# MCDU.net
KiCad netlist of a schematic drawn in EAGLE
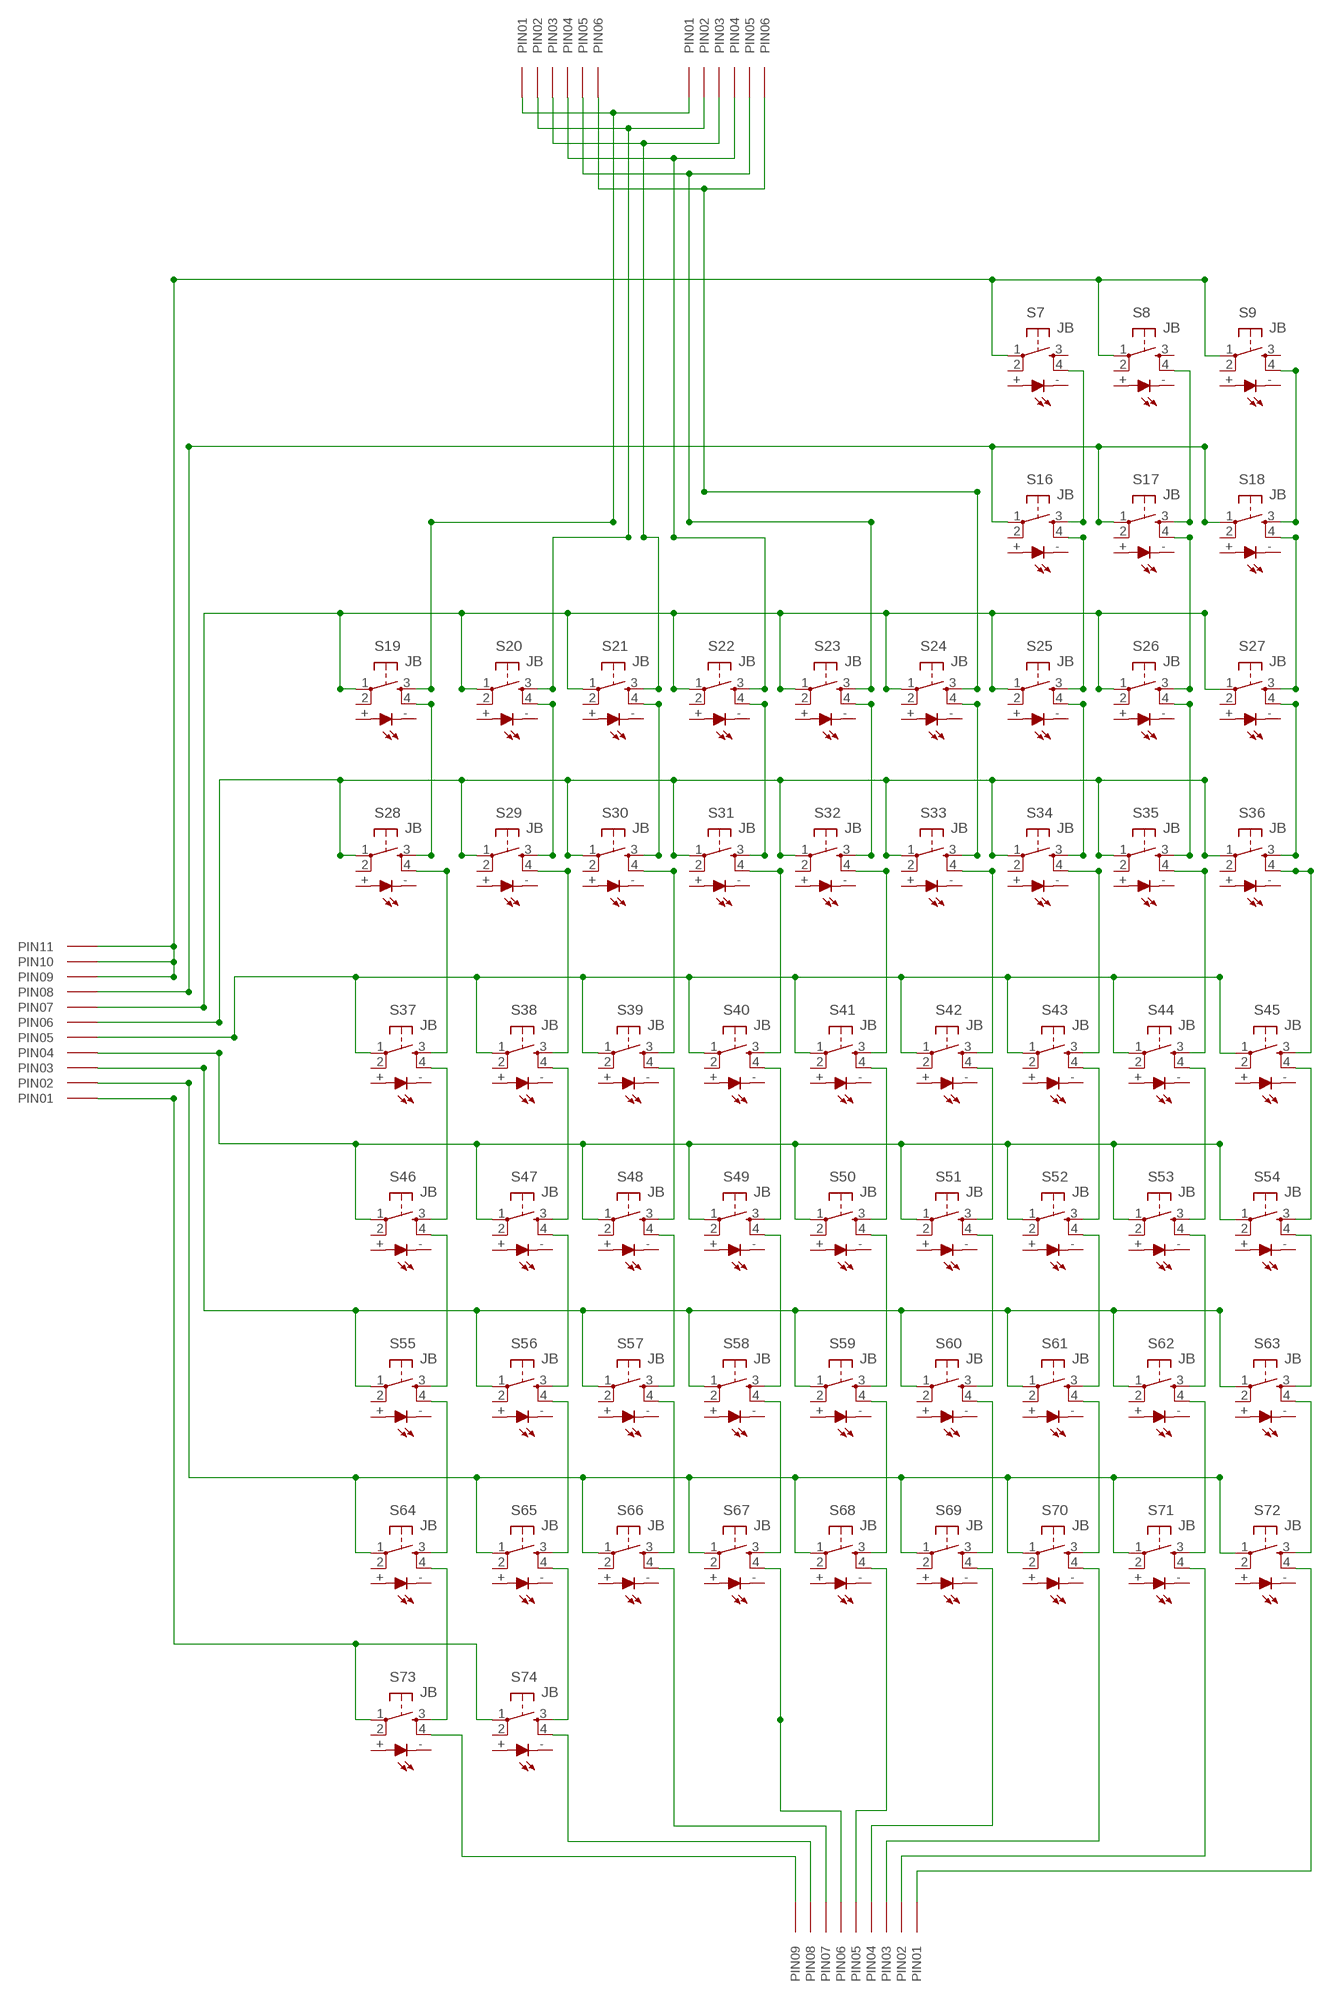
[diagram p0: schematic, sheet 1]

(export (version "E")
  (design (tool "Eeschema 10.0.6"))
  (components
    (comp (ref "S7") (value "JB") (footprint "eagle-import:JB") (libsource (lib "eagle-import") (part "JB")))
    (comp (ref "S8") (value "JB") (footprint "eagle-import:JB") (libsource (lib "eagle-import") (part "JB")))
    (comp (ref "S9") (value "JB") (footprint "eagle-import:JB") (libsource (lib "eagle-import") (part "JB")))
    (comp (ref "S16") (value "JB") (footprint "eagle-import:JB") (libsource (lib "eagle-import") (part "JB")))
    (comp (ref "S17") (value "JB") (footprint "eagle-import:JB") (libsource (lib "eagle-import") (part "JB")))
    (comp (ref "S18") (value "JB") (footprint "eagle-import:JB") (libsource (lib "eagle-import") (part "JB")))
    (comp (ref "S19") (value "JB") (footprint "eagle-import:JB") (libsource (lib "eagle-import") (part "JB")))
    (comp (ref "S20") (value "JB") (footprint "eagle-import:JB") (libsource (lib "eagle-import") (part "JB")))
    (comp (ref "S21") (value "JB") (footprint "eagle-import:JB") (libsource (lib "eagle-import") (part "JB")))
    (comp (ref "S22") (value "JB") (footprint "eagle-import:JB") (libsource (lib "eagle-import") (part "JB")))
    (comp (ref "S23") (value "JB") (footprint "eagle-import:JB") (libsource (lib "eagle-import") (part "JB")))
    (comp (ref "S24") (value "JB") (footprint "eagle-import:JB") (libsource (lib "eagle-import") (part "JB")))
    (comp (ref "S25") (value "JB") (footprint "eagle-import:JB") (libsource (lib "eagle-import") (part "JB")))
    (comp (ref "S26") (value "JB") (footprint "eagle-import:JB") (libsource (lib "eagle-import") (part "JB")))
    (comp (ref "S27") (value "JB") (footprint "eagle-import:JB") (libsource (lib "eagle-import") (part "JB")))
    (comp (ref "S28") (value "JB") (footprint "eagle-import:JB") (libsource (lib "eagle-import") (part "JB")))
    (comp (ref "S29") (value "JB") (footprint "eagle-import:JB") (libsource (lib "eagle-import") (part "JB")))
    (comp (ref "S30") (value "JB") (footprint "eagle-import:JB") (libsource (lib "eagle-import") (part "JB")))
    (comp (ref "S31") (value "JB") (footprint "eagle-import:JB") (libsource (lib "eagle-import") (part "JB")))
    (comp (ref "S32") (value "JB") (footprint "eagle-import:JB") (libsource (lib "eagle-import") (part "JB")))
    (comp (ref "S33") (value "JB") (footprint "eagle-import:JB") (libsource (lib "eagle-import") (part "JB")))
    (comp (ref "S34") (value "JB") (footprint "eagle-import:JB") (libsource (lib "eagle-import") (part "JB")))
    (comp (ref "S35") (value "JB") (footprint "eagle-import:JB") (libsource (lib "eagle-import") (part "JB")))
    (comp (ref "S36") (value "JB") (footprint "eagle-import:JB") (libsource (lib "eagle-import") (part "JB")))
    (comp (ref "S37") (value "JB") (footprint "eagle-import:JB") (libsource (lib "eagle-import") (part "JB")))
    (comp (ref "S38") (value "JB") (footprint "eagle-import:JB") (libsource (lib "eagle-import") (part "JB")))
    (comp (ref "S39") (value "JB") (footprint "eagle-import:JB") (libsource (lib "eagle-import") (part "JB")))
    (comp (ref "S40") (value "JB") (footprint "eagle-import:JB") (libsource (lib "eagle-import") (part "JB")))
    (comp (ref "S41") (value "JB") (footprint "eagle-import:JB") (libsource (lib "eagle-import") (part "JB")))
    (comp (ref "S42") (value "JB") (footprint "eagle-import:JB") (libsource (lib "eagle-import") (part "JB")))
    (comp (ref "S43") (value "JB") (footprint "eagle-import:JB") (libsource (lib "eagle-import") (part "JB")))
    (comp (ref "S44") (value "JB") (footprint "eagle-import:JB") (libsource (lib "eagle-import") (part "JB")))
    (comp (ref "S45") (value "JB") (footprint "eagle-import:JB") (libsource (lib "eagle-import") (part "JB")))
    (comp (ref "S46") (value "JB") (footprint "eagle-import:JB") (libsource (lib "eagle-import") (part "JB")))
    (comp (ref "S47") (value "JB") (footprint "eagle-import:JB") (libsource (lib "eagle-import") (part "JB")))
    (comp (ref "S48") (value "JB") (footprint "eagle-import:JB") (libsource (lib "eagle-import") (part "JB")))
    (comp (ref "S49") (value "JB") (footprint "eagle-import:JB") (libsource (lib "eagle-import") (part "JB")))
    (comp (ref "S50") (value "JB") (footprint "eagle-import:JB") (libsource (lib "eagle-import") (part "JB")))
    (comp (ref "S51") (value "JB") (footprint "eagle-import:JB") (libsource (lib "eagle-import") (part "JB")))
    (comp (ref "S52") (value "JB") (footprint "eagle-import:JB") (libsource (lib "eagle-import") (part "JB")))
    (comp (ref "S53") (value "JB") (footprint "eagle-import:JB") (libsource (lib "eagle-import") (part "JB")))
    (comp (ref "S54") (value "JB") (footprint "eagle-import:JB") (libsource (lib "eagle-import") (part "JB")))
    (comp (ref "S55") (value "JB") (footprint "eagle-import:JB") (libsource (lib "eagle-import") (part "JB")))
    (comp (ref "S56") (value "JB") (footprint "eagle-import:JB") (libsource (lib "eagle-import") (part "JB")))
    (comp (ref "S57") (value "JB") (footprint "eagle-import:JB") (libsource (lib "eagle-import") (part "JB")))
    (comp (ref "S58") (value "JB") (footprint "eagle-import:JB") (libsource (lib "eagle-import") (part "JB")))
    (comp (ref "S59") (value "JB") (footprint "eagle-import:JB") (libsource (lib "eagle-import") (part "JB")))
    (comp (ref "S60") (value "JB") (footprint "eagle-import:JB") (libsource (lib "eagle-import") (part "JB")))
    (comp (ref "S61") (value "JB") (footprint "eagle-import:JB") (libsource (lib "eagle-import") (part "JB")))
    (comp (ref "S62") (value "JB") (footprint "eagle-import:JB") (libsource (lib "eagle-import") (part "JB")))
    (comp (ref "S63") (value "JB") (footprint "eagle-import:JB") (libsource (lib "eagle-import") (part "JB")))
    (comp (ref "S64") (value "JB") (footprint "eagle-import:JB") (libsource (lib "eagle-import") (part "JB")))
    (comp (ref "S65") (value "JB") (footprint "eagle-import:JB") (libsource (lib "eagle-import") (part "JB")))
    (comp (ref "S66") (value "JB") (footprint "eagle-import:JB") (libsource (lib "eagle-import") (part "JB")))
    (comp (ref "S67") (value "JB") (footprint "eagle-import:JB") (libsource (lib "eagle-import") (part "JB")))
    (comp (ref "S68") (value "JB") (footprint "eagle-import:JB") (libsource (lib "eagle-import") (part "JB")))
    (comp (ref "S69") (value "JB") (footprint "eagle-import:JB") (libsource (lib "eagle-import") (part "JB")))
    (comp (ref "S70") (value "JB") (footprint "eagle-import:JB") (libsource (lib "eagle-import") (part "JB")))
    (comp (ref "S71") (value "JB") (footprint "eagle-import:JB") (libsource (lib "eagle-import") (part "JB")))
    (comp (ref "S72") (value "JB") (footprint "eagle-import:JB") (libsource (lib "eagle-import") (part "JB")))
    (comp (ref "S73") (value "JB") (footprint "eagle-import:JB") (libsource (lib "eagle-import") (part "JB")))
    (comp (ref "S74") (value "JB") (footprint "eagle-import:JB") (libsource (lib "eagle-import") (part "JB")))
    (comp (ref "U$2")
      (value "11PINOS")
      (footprint "eagle-import:11PINOS")
      (libsource (lib "eagle-import") (part "11PINOS"))
    )
    (comp (ref "U$3")
      (value "09PINOS")
      (footprint "eagle-import:09PINOS")
      (libsource (lib "eagle-import") (part "09PINOS"))
    )
    (comp (ref "U$5")
      (value "06PINOS")
      (footprint "eagle-import:06PINOS")
      (libsource (lib "eagle-import") (part "06PINOS"))
    )
    (comp (ref "U$6")
      (value "06PINOS")
      (footprint "eagle-import:06PINOS")
      (libsource (lib "eagle-import") (part "06PINOS"))
    )
  )
  (nets
    (net (code "1") (name "Net-(S7-P)") (class "Default")
      (node (ref "S7") (pin "1") (pinfunction "P_1") (pintype "passive"))
      (node (ref "S8") (pin "1") (pinfunction "P_1") (pintype "passive"))
      (node (ref "S9") (pin "1") (pinfunction "P_1") (pintype "passive"))
      (node (ref "U$2") (pin "PIN09") (pinfunction "PIN09_PIN09") (pintype "bidirectional"))
      (node (ref "U$2") (pin "PIN10") (pinfunction "PIN10_PIN10") (pintype "bidirectional"))
      (node (ref "U$2") (pin "PIN11") (pinfunction "PIN11_PIN11") (pintype "bidirectional"))
    )
    (net (code "2") (name "Net-(S16-P)") (class "Default")
      (node (ref "S16") (pin "1") (pinfunction "P_1") (pintype "passive"))
      (node (ref "S17") (pin "1") (pinfunction "P_1") (pintype "passive"))
      (node (ref "S18") (pin "1") (pinfunction "P_1") (pintype "passive"))
      (node (ref "U$2") (pin "PIN08") (pinfunction "PIN08_PIN08") (pintype "bidirectional"))
    )
    (net (code "3") (name "Net-(S16-S)") (class "Default")
      (node (ref "S16") (pin "3") (pinfunction "S_3") (pintype "passive"))
      (node (ref "S7") (pin "4") (pinfunction "S1_4") (pintype "passive"))
    )
    (net (code "4") (name "Net-(S16-S1)") (class "Default")
      (node (ref "S16") (pin "4") (pinfunction "S1_4") (pintype "passive"))
      (node (ref "S25") (pin "3") (pinfunction "S_3") (pintype "passive"))
    )
    (net (code "5") (name "Net-(S17-S)") (class "Default")
      (node (ref "S17") (pin "3") (pinfunction "S_3") (pintype "passive"))
      (node (ref "S8") (pin "4") (pinfunction "S1_4") (pintype "passive"))
    )
    (net (code "6") (name "Net-(S17-S1)") (class "Default")
      (node (ref "S17") (pin "4") (pinfunction "S1_4") (pintype "passive"))
      (node (ref "S26") (pin "3") (pinfunction "S_3") (pintype "passive"))
    )
    (net (code "7") (name "Net-(S18-S)") (class "Default")
      (node (ref "S18") (pin "3") (pinfunction "S_3") (pintype "passive"))
      (node (ref "S9") (pin "4") (pinfunction "S1_4") (pintype "passive"))
    )
    (net (code "8") (name "Net-(S18-S1)") (class "Default")
      (node (ref "S18") (pin "4") (pinfunction "S1_4") (pintype "passive"))
      (node (ref "S27") (pin "3") (pinfunction "S_3") (pintype "passive"))
    )
    (net (code "9") (name "Net-(S19-P)") (class "Default")
      (node (ref "S19") (pin "1") (pinfunction "P_1") (pintype "passive"))
      (node (ref "S20") (pin "1") (pinfunction "P_1") (pintype "passive"))
      (node (ref "S21") (pin "1") (pinfunction "P_1") (pintype "passive"))
      (node (ref "S22") (pin "1") (pinfunction "P_1") (pintype "passive"))
      (node (ref "S23") (pin "1") (pinfunction "P_1") (pintype "passive"))
      (node (ref "S24") (pin "1") (pinfunction "P_1") (pintype "passive"))
      (node (ref "S25") (pin "1") (pinfunction "P_1") (pintype "passive"))
      (node (ref "S26") (pin "1") (pinfunction "P_1") (pintype "passive"))
      (node (ref "S27") (pin "1") (pinfunction "P_1") (pintype "passive"))
      (node (ref "U$2") (pin "PIN07") (pinfunction "PIN07_PIN07") (pintype "bidirectional"))
    )
    (net (code "10") (name "Net-(S19-S)") (class "Default")
      (node (ref "S19") (pin "3") (pinfunction "S_3") (pintype "passive"))
      (node (ref "U$5") (pin "PIN01") (pinfunction "PIN01_PIN01") (pintype "bidirectional"))
      (node (ref "U$6") (pin "PIN01") (pinfunction "PIN01_PIN01") (pintype "bidirectional"))
    )
    (net (code "11") (name "Net-(S19-S1)") (class "Default")
      (node (ref "S19") (pin "4") (pinfunction "S1_4") (pintype "passive"))
      (node (ref "S28") (pin "3") (pinfunction "S_3") (pintype "passive"))
    )
    (net (code "12") (name "Net-(S20-S)") (class "Default")
      (node (ref "S20") (pin "3") (pinfunction "S_3") (pintype "passive"))
      (node (ref "U$5") (pin "PIN02") (pinfunction "PIN02_PIN02") (pintype "bidirectional"))
      (node (ref "U$6") (pin "PIN02") (pinfunction "PIN02_PIN02") (pintype "bidirectional"))
    )
    (net (code "13") (name "Net-(S20-S1)") (class "Default")
      (node (ref "S20") (pin "4") (pinfunction "S1_4") (pintype "passive"))
      (node (ref "S29") (pin "3") (pinfunction "S_3") (pintype "passive"))
    )
    (net (code "14") (name "Net-(S21-S)") (class "Default")
      (node (ref "S21") (pin "3") (pinfunction "S_3") (pintype "passive"))
      (node (ref "U$5") (pin "PIN03") (pinfunction "PIN03_PIN03") (pintype "bidirectional"))
      (node (ref "U$6") (pin "PIN03") (pinfunction "PIN03_PIN03") (pintype "bidirectional"))
    )
    (net (code "15") (name "Net-(S21-S1)") (class "Default")
      (node (ref "S21") (pin "4") (pinfunction "S1_4") (pintype "passive"))
      (node (ref "S30") (pin "3") (pinfunction "S_3") (pintype "passive"))
    )
    (net (code "16") (name "Net-(S22-S)") (class "Default")
      (node (ref "S22") (pin "3") (pinfunction "S_3") (pintype "passive"))
      (node (ref "U$5") (pin "PIN04") (pinfunction "PIN04_PIN04") (pintype "bidirectional"))
      (node (ref "U$6") (pin "PIN04") (pinfunction "PIN04_PIN04") (pintype "bidirectional"))
    )
    (net (code "17") (name "Net-(S22-S1)") (class "Default")
      (node (ref "S22") (pin "4") (pinfunction "S1_4") (pintype "passive"))
      (node (ref "S31") (pin "3") (pinfunction "S_3") (pintype "passive"))
    )
    (net (code "18") (name "Net-(S23-S)") (class "Default")
      (node (ref "S23") (pin "3") (pinfunction "S_3") (pintype "passive"))
      (node (ref "U$5") (pin "PIN05") (pinfunction "PIN05_PIN05") (pintype "bidirectional"))
      (node (ref "U$6") (pin "PIN05") (pinfunction "PIN05_PIN05") (pintype "bidirectional"))
    )
    (net (code "19") (name "Net-(S23-S1)") (class "Default")
      (node (ref "S23") (pin "4") (pinfunction "S1_4") (pintype "passive"))
      (node (ref "S32") (pin "3") (pinfunction "S_3") (pintype "passive"))
    )
    (net (code "20") (name "Net-(S24-S)") (class "Default")
      (node (ref "S24") (pin "3") (pinfunction "S_3") (pintype "passive"))
      (node (ref "U$5") (pin "PIN06") (pinfunction "PIN06_PIN06") (pintype "bidirectional"))
      (node (ref "U$6") (pin "PIN06") (pinfunction "PIN06_PIN06") (pintype "bidirectional"))
    )
    (net (code "21") (name "Net-(S24-S1)") (class "Default")
      (node (ref "S24") (pin "4") (pinfunction "S1_4") (pintype "passive"))
      (node (ref "S33") (pin "3") (pinfunction "S_3") (pintype "passive"))
    )
    (net (code "22") (name "Net-(S25-S1)") (class "Default")
      (node (ref "S25") (pin "4") (pinfunction "S1_4") (pintype "passive"))
      (node (ref "S34") (pin "3") (pinfunction "S_3") (pintype "passive"))
    )
    (net (code "23") (name "Net-(S26-S1)") (class "Default")
      (node (ref "S26") (pin "4") (pinfunction "S1_4") (pintype "passive"))
      (node (ref "S35") (pin "3") (pinfunction "S_3") (pintype "passive"))
    )
    (net (code "24") (name "Net-(S27-S1)") (class "Default")
      (node (ref "S27") (pin "4") (pinfunction "S1_4") (pintype "passive"))
      (node (ref "S36") (pin "3") (pinfunction "S_3") (pintype "passive"))
    )
    (net (code "25") (name "Net-(S28-P)") (class "Default")
      (node (ref "S28") (pin "1") (pinfunction "P_1") (pintype "passive"))
      (node (ref "S29") (pin "1") (pinfunction "P_1") (pintype "passive"))
      (node (ref "S30") (pin "1") (pinfunction "P_1") (pintype "passive"))
      (node (ref "S31") (pin "1") (pinfunction "P_1") (pintype "passive"))
      (node (ref "S32") (pin "1") (pinfunction "P_1") (pintype "passive"))
      (node (ref "S33") (pin "1") (pinfunction "P_1") (pintype "passive"))
      (node (ref "S34") (pin "1") (pinfunction "P_1") (pintype "passive"))
      (node (ref "S35") (pin "1") (pinfunction "P_1") (pintype "passive"))
      (node (ref "S36") (pin "1") (pinfunction "P_1") (pintype "passive"))
      (node (ref "U$2") (pin "PIN06") (pinfunction "PIN06_PIN06") (pintype "bidirectional"))
    )
    (net (code "26") (name "Net-(S28-S1)") (class "Default")
      (node (ref "S28") (pin "4") (pinfunction "S1_4") (pintype "passive"))
      (node (ref "S37") (pin "3") (pinfunction "S_3") (pintype "passive"))
    )
    (net (code "27") (name "Net-(S29-S1)") (class "Default")
      (node (ref "S29") (pin "4") (pinfunction "S1_4") (pintype "passive"))
      (node (ref "S38") (pin "3") (pinfunction "S_3") (pintype "passive"))
    )
    (net (code "28") (name "Net-(S30-S1)") (class "Default")
      (node (ref "S30") (pin "4") (pinfunction "S1_4") (pintype "passive"))
      (node (ref "S39") (pin "3") (pinfunction "S_3") (pintype "passive"))
    )
    (net (code "29") (name "Net-(S31-S1)") (class "Default")
      (node (ref "S31") (pin "4") (pinfunction "S1_4") (pintype "passive"))
      (node (ref "S40") (pin "3") (pinfunction "S_3") (pintype "passive"))
    )
    (net (code "30") (name "Net-(S32-S1)") (class "Default")
      (node (ref "S32") (pin "4") (pinfunction "S1_4") (pintype "passive"))
      (node (ref "S41") (pin "3") (pinfunction "S_3") (pintype "passive"))
    )
    (net (code "31") (name "Net-(S33-S1)") (class "Default")
      (node (ref "S33") (pin "4") (pinfunction "S1_4") (pintype "passive"))
      (node (ref "S42") (pin "3") (pinfunction "S_3") (pintype "passive"))
    )
    (net (code "32") (name "Net-(S34-S1)") (class "Default")
      (node (ref "S34") (pin "4") (pinfunction "S1_4") (pintype "passive"))
      (node (ref "S43") (pin "3") (pinfunction "S_3") (pintype "passive"))
    )
    (net (code "33") (name "Net-(S35-S1)") (class "Default")
      (node (ref "S35") (pin "4") (pinfunction "S1_4") (pintype "passive"))
      (node (ref "S44") (pin "3") (pinfunction "S_3") (pintype "passive"))
    )
    (net (code "34") (name "Net-(S36-S1)") (class "Default")
      (node (ref "S36") (pin "4") (pinfunction "S1_4") (pintype "passive"))
      (node (ref "S45") (pin "3") (pinfunction "S_3") (pintype "passive"))
    )
    (net (code "35") (name "Net-(S37-P)") (class "Default")
      (node (ref "S37") (pin "1") (pinfunction "P_1") (pintype "passive"))
      (node (ref "S38") (pin "1") (pinfunction "P_1") (pintype "passive"))
      (node (ref "S39") (pin "1") (pinfunction "P_1") (pintype "passive"))
      (node (ref "S40") (pin "1") (pinfunction "P_1") (pintype "passive"))
      (node (ref "S41") (pin "1") (pinfunction "P_1") (pintype "passive"))
      (node (ref "S42") (pin "1") (pinfunction "P_1") (pintype "passive"))
      (node (ref "S43") (pin "1") (pinfunction "P_1") (pintype "passive"))
      (node (ref "S44") (pin "1") (pinfunction "P_1") (pintype "passive"))
      (node (ref "S45") (pin "1") (pinfunction "P_1") (pintype "passive"))
      (node (ref "U$2") (pin "PIN05") (pinfunction "PIN05_PIN05") (pintype "bidirectional"))
    )
    (net (code "36") (name "Net-(S37-S1)") (class "Default")
      (node (ref "S37") (pin "4") (pinfunction "S1_4") (pintype "passive"))
      (node (ref "S46") (pin "3") (pinfunction "S_3") (pintype "passive"))
    )
    (net (code "37") (name "Net-(S38-S1)") (class "Default")
      (node (ref "S38") (pin "4") (pinfunction "S1_4") (pintype "passive"))
      (node (ref "S47") (pin "3") (pinfunction "S_3") (pintype "passive"))
    )
    (net (code "38") (name "Net-(S39-S1)") (class "Default")
      (node (ref "S39") (pin "4") (pinfunction "S1_4") (pintype "passive"))
      (node (ref "S48") (pin "3") (pinfunction "S_3") (pintype "passive"))
    )
    (net (code "39") (name "Net-(S40-S1)") (class "Default")
      (node (ref "S40") (pin "4") (pinfunction "S1_4") (pintype "passive"))
      (node (ref "S49") (pin "3") (pinfunction "S_3") (pintype "passive"))
    )
    (net (code "40") (name "Net-(S41-S1)") (class "Default")
      (node (ref "S41") (pin "4") (pinfunction "S1_4") (pintype "passive"))
      (node (ref "S50") (pin "3") (pinfunction "S_3") (pintype "passive"))
    )
    (net (code "41") (name "Net-(S42-S1)") (class "Default")
      (node (ref "S42") (pin "4") (pinfunction "S1_4") (pintype "passive"))
      (node (ref "S51") (pin "3") (pinfunction "S_3") (pintype "passive"))
    )
    (net (code "42") (name "Net-(S43-S1)") (class "Default")
      (node (ref "S43") (pin "4") (pinfunction "S1_4") (pintype "passive"))
      (node (ref "S52") (pin "3") (pinfunction "S_3") (pintype "passive"))
    )
    (net (code "43") (name "Net-(S44-S1)") (class "Default")
      (node (ref "S44") (pin "4") (pinfunction "S1_4") (pintype "passive"))
      (node (ref "S53") (pin "3") (pinfunction "S_3") (pintype "passive"))
    )
    (net (code "44") (name "Net-(S45-S1)") (class "Default")
      (node (ref "S45") (pin "4") (pinfunction "S1_4") (pintype "passive"))
      (node (ref "S54") (pin "3") (pinfunction "S_3") (pintype "passive"))
    )
    (net (code "45") (name "Net-(S46-P)") (class "Default")
      (node (ref "S46") (pin "1") (pinfunction "P_1") (pintype "passive"))
      (node (ref "S47") (pin "1") (pinfunction "P_1") (pintype "passive"))
      (node (ref "S48") (pin "1") (pinfunction "P_1") (pintype "passive"))
      (node (ref "S49") (pin "1") (pinfunction "P_1") (pintype "passive"))
      (node (ref "S50") (pin "1") (pinfunction "P_1") (pintype "passive"))
      (node (ref "S51") (pin "1") (pinfunction "P_1") (pintype "passive"))
      (node (ref "S52") (pin "1") (pinfunction "P_1") (pintype "passive"))
      (node (ref "S53") (pin "1") (pinfunction "P_1") (pintype "passive"))
      (node (ref "S54") (pin "1") (pinfunction "P_1") (pintype "passive"))
      (node (ref "U$2") (pin "PIN04") (pinfunction "PIN04_PIN04") (pintype "bidirectional"))
    )
    (net (code "46") (name "Net-(S46-S1)") (class "Default")
      (node (ref "S46") (pin "4") (pinfunction "S1_4") (pintype "passive"))
      (node (ref "S55") (pin "3") (pinfunction "S_3") (pintype "passive"))
    )
    (net (code "47") (name "Net-(S47-S1)") (class "Default")
      (node (ref "S47") (pin "4") (pinfunction "S1_4") (pintype "passive"))
      (node (ref "S56") (pin "3") (pinfunction "S_3") (pintype "passive"))
    )
    (net (code "48") (name "Net-(S48-S1)") (class "Default")
      (node (ref "S48") (pin "4") (pinfunction "S1_4") (pintype "passive"))
      (node (ref "S57") (pin "3") (pinfunction "S_3") (pintype "passive"))
    )
    (net (code "49") (name "Net-(S49-S1)") (class "Default")
      (node (ref "S49") (pin "4") (pinfunction "S1_4") (pintype "passive"))
      (node (ref "S58") (pin "3") (pinfunction "S_3") (pintype "passive"))
    )
    (net (code "50") (name "Net-(S50-S1)") (class "Default")
      (node (ref "S50") (pin "4") (pinfunction "S1_4") (pintype "passive"))
      (node (ref "S59") (pin "3") (pinfunction "S_3") (pintype "passive"))
    )
    (net (code "51") (name "Net-(S51-S1)") (class "Default")
      (node (ref "S51") (pin "4") (pinfunction "S1_4") (pintype "passive"))
      (node (ref "S60") (pin "3") (pinfunction "S_3") (pintype "passive"))
    )
    (net (code "52") (name "Net-(S52-S1)") (class "Default")
      (node (ref "S52") (pin "4") (pinfunction "S1_4") (pintype "passive"))
      (node (ref "S61") (pin "3") (pinfunction "S_3") (pintype "passive"))
    )
    (net (code "53") (name "Net-(S53-S1)") (class "Default")
      (node (ref "S53") (pin "4") (pinfunction "S1_4") (pintype "passive"))
      (node (ref "S62") (pin "3") (pinfunction "S_3") (pintype "passive"))
    )
    (net (code "54") (name "Net-(S54-S1)") (class "Default")
      (node (ref "S54") (pin "4") (pinfunction "S1_4") (pintype "passive"))
      (node (ref "S63") (pin "3") (pinfunction "S_3") (pintype "passive"))
    )
    (net (code "55") (name "Net-(S55-P)") (class "Default")
      (node (ref "S55") (pin "1") (pinfunction "P_1") (pintype "passive"))
      (node (ref "S56") (pin "1") (pinfunction "P_1") (pintype "passive"))
      (node (ref "S57") (pin "1") (pinfunction "P_1") (pintype "passive"))
      (node (ref "S58") (pin "1") (pinfunction "P_1") (pintype "passive"))
      (node (ref "S59") (pin "1") (pinfunction "P_1") (pintype "passive"))
      (node (ref "S60") (pin "1") (pinfunction "P_1") (pintype "passive"))
      (node (ref "S61") (pin "1") (pinfunction "P_1") (pintype "passive"))
      (node (ref "S62") (pin "1") (pinfunction "P_1") (pintype "passive"))
      (node (ref "S63") (pin "1") (pinfunction "P_1") (pintype "passive"))
      (node (ref "U$2") (pin "PIN03") (pinfunction "PIN03_PIN03") (pintype "bidirectional"))
    )
    (net (code "56") (name "Net-(S55-S1)") (class "Default")
      (node (ref "S55") (pin "4") (pinfunction "S1_4") (pintype "passive"))
      (node (ref "S64") (pin "3") (pinfunction "S_3") (pintype "passive"))
    )
    (net (code "57") (name "Net-(S56-S1)") (class "Default")
      (node (ref "S56") (pin "4") (pinfunction "S1_4") (pintype "passive"))
      (node (ref "S65") (pin "3") (pinfunction "S_3") (pintype "passive"))
    )
    (net (code "58") (name "Net-(S57-S1)") (class "Default")
      (node (ref "S57") (pin "4") (pinfunction "S1_4") (pintype "passive"))
      (node (ref "S66") (pin "3") (pinfunction "S_3") (pintype "passive"))
    )
    (net (code "59") (name "Net-(S58-S1)") (class "Default")
      (node (ref "S58") (pin "4") (pinfunction "S1_4") (pintype "passive"))
      (node (ref "S67") (pin "3") (pinfunction "S_3") (pintype "passive"))
    )
    (net (code "60") (name "Net-(S59-S1)") (class "Default")
      (node (ref "S59") (pin "4") (pinfunction "S1_4") (pintype "passive"))
      (node (ref "S68") (pin "3") (pinfunction "S_3") (pintype "passive"))
    )
    (net (code "61") (name "Net-(S60-S1)") (class "Default")
      (node (ref "S60") (pin "4") (pinfunction "S1_4") (pintype "passive"))
      (node (ref "S69") (pin "3") (pinfunction "S_3") (pintype "passive"))
    )
    (net (code "62") (name "Net-(S61-S1)") (class "Default")
      (node (ref "S61") (pin "4") (pinfunction "S1_4") (pintype "passive"))
      (node (ref "S70") (pin "3") (pinfunction "S_3") (pintype "passive"))
    )
    (net (code "63") (name "Net-(S62-S1)") (class "Default")
      (node (ref "S62") (pin "4") (pinfunction "S1_4") (pintype "passive"))
      (node (ref "S71") (pin "3") (pinfunction "S_3") (pintype "passive"))
    )
    (net (code "64") (name "Net-(S63-S1)") (class "Default")
      (node (ref "S63") (pin "4") (pinfunction "S1_4") (pintype "passive"))
      (node (ref "S72") (pin "3") (pinfunction "S_3") (pintype "passive"))
    )
    (net (code "65") (name "Net-(S64-P)") (class "Default")
      (node (ref "S64") (pin "1") (pinfunction "P_1") (pintype "passive"))
      (node (ref "S65") (pin "1") (pinfunction "P_1") (pintype "passive"))
      (node (ref "S66") (pin "1") (pinfunction "P_1") (pintype "passive"))
      (node (ref "S67") (pin "1") (pinfunction "P_1") (pintype "passive"))
      (node (ref "S68") (pin "1") (pinfunction "P_1") (pintype "passive"))
      (node (ref "S69") (pin "1") (pinfunction "P_1") (pintype "passive"))
      (node (ref "S70") (pin "1") (pinfunction "P_1") (pintype "passive"))
      (node (ref "S71") (pin "1") (pinfunction "P_1") (pintype "passive"))
      (node (ref "S72") (pin "1") (pinfunction "P_1") (pintype "passive"))
      (node (ref "U$2") (pin "PIN02") (pinfunction "PIN02_PIN02") (pintype "bidirectional"))
    )
    (net (code "66") (name "Net-(S64-S1)") (class "Default")
      (node (ref "S64") (pin "4") (pinfunction "S1_4") (pintype "passive"))
      (node (ref "S73") (pin "3") (pinfunction "S_3") (pintype "passive"))
    )
    (net (code "67") (name "Net-(S65-S1)") (class "Default")
      (node (ref "S65") (pin "4") (pinfunction "S1_4") (pintype "passive"))
      (node (ref "S74") (pin "3") (pinfunction "S_3") (pintype "passive"))
    )
    (net (code "68") (name "Net-(S66-S1)") (class "Default")
      (node (ref "S66") (pin "4") (pinfunction "S1_4") (pintype "passive"))
      (node (ref "U$3") (pin "PIN07") (pinfunction "PIN07_PIN07") (pintype "bidirectional"))
    )
    (net (code "69") (name "Net-(S67-S1)") (class "Default")
      (node (ref "S67") (pin "4") (pinfunction "S1_4") (pintype "passive"))
      (node (ref "U$3") (pin "PIN06") (pinfunction "PIN06_PIN06") (pintype "bidirectional"))
    )
    (net (code "70") (name "Net-(S68-S1)") (class "Default")
      (node (ref "S68") (pin "4") (pinfunction "S1_4") (pintype "passive"))
      (node (ref "U$3") (pin "PIN05") (pinfunction "PIN05_PIN05") (pintype "bidirectional"))
    )
    (net (code "71") (name "Net-(S69-S1)") (class "Default")
      (node (ref "S69") (pin "4") (pinfunction "S1_4") (pintype "passive"))
      (node (ref "U$3") (pin "PIN04") (pinfunction "PIN04_PIN04") (pintype "bidirectional"))
    )
    (net (code "72") (name "Net-(S70-S1)") (class "Default")
      (node (ref "S70") (pin "4") (pinfunction "S1_4") (pintype "passive"))
      (node (ref "U$3") (pin "PIN03") (pinfunction "PIN03_PIN03") (pintype "bidirectional"))
    )
    (net (code "73") (name "Net-(S71-S1)") (class "Default")
      (node (ref "S71") (pin "4") (pinfunction "S1_4") (pintype "passive"))
      (node (ref "U$3") (pin "PIN02") (pinfunction "PIN02_PIN02") (pintype "bidirectional"))
    )
    (net (code "74") (name "Net-(S72-S1)") (class "Default")
      (node (ref "S72") (pin "4") (pinfunction "S1_4") (pintype "passive"))
      (node (ref "U$3") (pin "PIN01") (pinfunction "PIN01_PIN01") (pintype "bidirectional"))
    )
    (net (code "75") (name "Net-(S73-P)") (class "Default")
      (node (ref "S73") (pin "1") (pinfunction "P_1") (pintype "passive"))
      (node (ref "S74") (pin "1") (pinfunction "P_1") (pintype "passive"))
      (node (ref "U$2") (pin "PIN01") (pinfunction "PIN01_PIN01") (pintype "bidirectional"))
    )
    (net (code "76") (name "Net-(S73-S1)") (class "Default")
      (node (ref "S73") (pin "4") (pinfunction "S1_4") (pintype "passive"))
      (node (ref "U$3") (pin "PIN09") (pinfunction "PIN09_PIN09") (pintype "bidirectional"))
    )
    (net (code "77") (name "Net-(S74-S1)") (class "Default")
      (node (ref "S74") (pin "4") (pinfunction "S1_4") (pintype "passive"))
      (node (ref "U$3") (pin "PIN08") (pinfunction "PIN08_PIN08") (pintype "bidirectional"))
    )
    (net (code "78") (name "unconnected-(S7-A-Pad+)") (class "Default")
      (node (ref "S7") (pin "+") (pinfunction "A_+") (pintype "passive"))
    )
    (net (code "79") (name "unconnected-(S7-C-Pad-)") (class "Default")
      (node (ref "S7") (pin "-") (pinfunction "C_-") (pintype "passive"))
    )
    (net (code "80") (name "unconnected-(S7-P1-Pad2)") (class "Default")
      (node (ref "S7") (pin "2") (pinfunction "P1_2") (pintype "passive"))
    )
    (net (code "81") (name "unconnected-(S7-S-Pad3)") (class "Default")
      (node (ref "S7") (pin "3") (pinfunction "S_3") (pintype "passive"))
    )
    (net (code "82") (name "unconnected-(S8-A-Pad+)") (class "Default")
      (node (ref "S8") (pin "+") (pinfunction "A_+") (pintype "passive"))
    )
    (net (code "83") (name "unconnected-(S8-C-Pad-)") (class "Default")
      (node (ref "S8") (pin "-") (pinfunction "C_-") (pintype "passive"))
    )
    (net (code "84") (name "unconnected-(S8-P1-Pad2)") (class "Default")
      (node (ref "S8") (pin "2") (pinfunction "P1_2") (pintype "passive"))
    )
    (net (code "85") (name "unconnected-(S8-S-Pad3)") (class "Default")
      (node (ref "S8") (pin "3") (pinfunction "S_3") (pintype "passive"))
    )
    (net (code "86") (name "unconnected-(S9-A-Pad+)") (class "Default")
      (node (ref "S9") (pin "+") (pinfunction "A_+") (pintype "passive"))
    )
    (net (code "87") (name "unconnected-(S9-C-Pad-)") (class "Default")
      (node (ref "S9") (pin "-") (pinfunction "C_-") (pintype "passive"))
    )
    (net (code "88") (name "unconnected-(S9-P1-Pad2)") (class "Default")
      (node (ref "S9") (pin "2") (pinfunction "P1_2") (pintype "passive"))
    )
    (net (code "89") (name "unconnected-(S9-S-Pad3)") (class "Default")
      (node (ref "S9") (pin "3") (pinfunction "S_3") (pintype "passive"))
    )
    (net (code "90") (name "unconnected-(S16-A-Pad+)") (class "Default")
      (node (ref "S16") (pin "+") (pinfunction "A_+") (pintype "passive"))
    )
    (net (code "91") (name "unconnected-(S16-C-Pad-)") (class "Default")
      (node (ref "S16") (pin "-") (pinfunction "C_-") (pintype "passive"))
    )
    (net (code "92") (name "unconnected-(S16-P1-Pad2)") (class "Default")
      (node (ref "S16") (pin "2") (pinfunction "P1_2") (pintype "passive"))
    )
    (net (code "93") (name "unconnected-(S17-A-Pad+)") (class "Default")
      (node (ref "S17") (pin "+") (pinfunction "A_+") (pintype "passive"))
    )
    (net (code "94") (name "unconnected-(S17-C-Pad-)") (class "Default")
      (node (ref "S17") (pin "-") (pinfunction "C_-") (pintype "passive"))
    )
    (net (code "95") (name "unconnected-(S17-P1-Pad2)") (class "Default")
      (node (ref "S17") (pin "2") (pinfunction "P1_2") (pintype "passive"))
    )
    (net (code "96") (name "unconnected-(S18-A-Pad+)") (class "Default")
      (node (ref "S18") (pin "+") (pinfunction "A_+") (pintype "passive"))
    )
    (net (code "97") (name "unconnected-(S18-C-Pad-)") (class "Default")
      (node (ref "S18") (pin "-") (pinfunction "C_-") (pintype "passive"))
    )
    (net (code "98") (name "unconnected-(S18-P1-Pad2)") (class "Default")
      (node (ref "S18") (pin "2") (pinfunction "P1_2") (pintype "passive"))
    )
    (net (code "99") (name "unconnected-(S19-A-Pad+)") (class "Default")
      (node (ref "S19") (pin "+") (pinfunction "A_+") (pintype "passive"))
    )
    (net (code "100") (name "unconnected-(S19-C-Pad-)") (class "Default")
      (node (ref "S19") (pin "-") (pinfunction "C_-") (pintype "passive"))
    )
    (net (code "101") (name "unconnected-(S19-P1-Pad2)") (class "Default")
      (node (ref "S19") (pin "2") (pinfunction "P1_2") (pintype "passive"))
    )
    (net (code "102") (name "unconnected-(S20-A-Pad+)") (class "Default")
      (node (ref "S20") (pin "+") (pinfunction "A_+") (pintype "passive"))
    )
    (net (code "103") (name "unconnected-(S20-C-Pad-)") (class "Default")
      (node (ref "S20") (pin "-") (pinfunction "C_-") (pintype "passive"))
    )
    (net (code "104") (name "unconnected-(S20-P1-Pad2)") (class "Default")
      (node (ref "S20") (pin "2") (pinfunction "P1_2") (pintype "passive"))
    )
    (net (code "105") (name "unconnected-(S21-A-Pad+)") (class "Default")
      (node (ref "S21") (pin "+") (pinfunction "A_+") (pintype "passive"))
    )
    (net (code "106") (name "unconnected-(S21-C-Pad-)") (class "Default")
      (node (ref "S21") (pin "-") (pinfunction "C_-") (pintype "passive"))
    )
    (net (code "107") (name "unconnected-(S21-P1-Pad2)") (class "Default")
      (node (ref "S21") (pin "2") (pinfunction "P1_2") (pintype "passive"))
    )
    (net (code "108") (name "unconnected-(S22-A-Pad+)") (class "Default")
      (node (ref "S22") (pin "+") (pinfunction "A_+") (pintype "passive"))
    )
    (net (code "109") (name "unconnected-(S22-C-Pad-)") (class "Default")
      (node (ref "S22") (pin "-") (pinfunction "C_-") (pintype "passive"))
    )
    (net (code "110") (name "unconnected-(S22-P1-Pad2)") (class "Default")
      (node (ref "S22") (pin "2") (pinfunction "P1_2") (pintype "passive"))
    )
    (net (code "111") (name "unconnected-(S23-A-Pad+)") (class "Default")
      (node (ref "S23") (pin "+") (pinfunction "A_+") (pintype "passive"))
    )
    (net (code "112") (name "unconnected-(S23-C-Pad-)") (class "Default")
      (node (ref "S23") (pin "-") (pinfunction "C_-") (pintype "passive"))
    )
    (net (code "113") (name "unconnected-(S23-P1-Pad2)") (class "Default")
      (node (ref "S23") (pin "2") (pinfunction "P1_2") (pintype "passive"))
    )
    (net (code "114") (name "unconnected-(S24-A-Pad+)") (class "Default")
      (node (ref "S24") (pin "+") (pinfunction "A_+") (pintype "passive"))
    )
    (net (code "115") (name "unconnected-(S24-C-Pad-)") (class "Default")
      (node (ref "S24") (pin "-") (pinfunction "C_-") (pintype "passive"))
    )
    (net (code "116") (name "unconnected-(S24-P1-Pad2)") (class "Default")
      (node (ref "S24") (pin "2") (pinfunction "P1_2") (pintype "passive"))
    )
    (net (code "117") (name "unconnected-(S25-A-Pad+)") (class "Default")
      (node (ref "S25") (pin "+") (pinfunction "A_+") (pintype "passive"))
    )
    (net (code "118") (name "unconnected-(S25-C-Pad-)") (class "Default")
      (node (ref "S25") (pin "-") (pinfunction "C_-") (pintype "passive"))
    )
    (net (code "119") (name "unconnected-(S25-P1-Pad2)") (class "Default")
      (node (ref "S25") (pin "2") (pinfunction "P1_2") (pintype "passive"))
    )
    (net (code "120") (name "unconnected-(S26-A-Pad+)") (class "Default")
      (node (ref "S26") (pin "+") (pinfunction "A_+") (pintype "passive"))
    )
    (net (code "121") (name "unconnected-(S26-C-Pad-)") (class "Default")
      (node (ref "S26") (pin "-") (pinfunction "C_-") (pintype "passive"))
    )
    (net (code "122") (name "unconnected-(S26-P1-Pad2)") (class "Default")
      (node (ref "S26") (pin "2") (pinfunction "P1_2") (pintype "passive"))
    )
    (net (code "123") (name "unconnected-(S27-A-Pad+)") (class "Default")
      (node (ref "S27") (pin "+") (pinfunction "A_+") (pintype "passive"))
    )
    (net (code "124") (name "unconnected-(S27-C-Pad-)") (class "Default")
      (node (ref "S27") (pin "-") (pinfunction "C_-") (pintype "passive"))
    )
    (net (code "125") (name "unconnected-(S27-P1-Pad2)") (class "Default")
      (node (ref "S27") (pin "2") (pinfunction "P1_2") (pintype "passive"))
    )
    (net (code "126") (name "unconnected-(S28-A-Pad+)") (class "Default")
      (node (ref "S28") (pin "+") (pinfunction "A_+") (pintype "passive"))
    )
    (net (code "127") (name "unconnected-(S28-C-Pad-)") (class "Default")
      (node (ref "S28") (pin "-") (pinfunction "C_-") (pintype "passive"))
    )
    (net (code "128") (name "unconnected-(S28-P1-Pad2)") (class "Default")
      (node (ref "S28") (pin "2") (pinfunction "P1_2") (pintype "passive"))
    )
    (net (code "129") (name "unconnected-(S29-A-Pad+)") (class "Default")
      (node (ref "S29") (pin "+") (pinfunction "A_+") (pintype "passive"))
    )
    (net (code "130") (name "unconnected-(S29-C-Pad-)") (class "Default")
      (node (ref "S29") (pin "-") (pinfunction "C_-") (pintype "passive"))
    )
    (net (code "131") (name "unconnected-(S29-P1-Pad2)") (class "Default")
      (node (ref "S29") (pin "2") (pinfunction "P1_2") (pintype "passive"))
    )
    (net (code "132") (name "unconnected-(S30-A-Pad+)") (class "Default")
      (node (ref "S30") (pin "+") (pinfunction "A_+") (pintype "passive"))
    )
    (net (code "133") (name "unconnected-(S30-C-Pad-)") (class "Default")
      (node (ref "S30") (pin "-") (pinfunction "C_-") (pintype "passive"))
    )
    (net (code "134") (name "unconnected-(S30-P1-Pad2)") (class "Default")
      (node (ref "S30") (pin "2") (pinfunction "P1_2") (pintype "passive"))
    )
    (net (code "135") (name "unconnected-(S31-A-Pad+)") (class "Default")
      (node (ref "S31") (pin "+") (pinfunction "A_+") (pintype "passive"))
    )
    (net (code "136") (name "unconnected-(S31-C-Pad-)") (class "Default")
      (node (ref "S31") (pin "-") (pinfunction "C_-") (pintype "passive"))
    )
    (net (code "137") (name "unconnected-(S31-P1-Pad2)") (class "Default")
      (node (ref "S31") (pin "2") (pinfunction "P1_2") (pintype "passive"))
    )
    (net (code "138") (name "unconnected-(S32-A-Pad+)") (class "Default")
      (node (ref "S32") (pin "+") (pinfunction "A_+") (pintype "passive"))
    )
    (net (code "139") (name "unconnected-(S32-C-Pad-)") (class "Default")
      (node (ref "S32") (pin "-") (pinfunction "C_-") (pintype "passive"))
    )
    (net (code "140") (name "unconnected-(S32-P1-Pad2)") (class "Default")
      (node (ref "S32") (pin "2") (pinfunction "P1_2") (pintype "passive"))
    )
    (net (code "141") (name "unconnected-(S33-A-Pad+)") (class "Default")
      (node (ref "S33") (pin "+") (pinfunction "A_+") (pintype "passive"))
    )
    (net (code "142") (name "unconnected-(S33-C-Pad-)") (class "Default")
      (node (ref "S33") (pin "-") (pinfunction "C_-") (pintype "passive"))
    )
    (net (code "143") (name "unconnected-(S33-P1-Pad2)") (class "Default")
      (node (ref "S33") (pin "2") (pinfunction "P1_2") (pintype "passive"))
    )
    (net (code "144") (name "unconnected-(S34-A-Pad+)") (class "Default")
      (node (ref "S34") (pin "+") (pinfunction "A_+") (pintype "passive"))
    )
    (net (code "145") (name "unconnected-(S34-C-Pad-)") (class "Default")
      (node (ref "S34") (pin "-") (pinfunction "C_-") (pintype "passive"))
    )
    (net (code "146") (name "unconnected-(S34-P1-Pad2)") (class "Default")
      (node (ref "S34") (pin "2") (pinfunction "P1_2") (pintype "passive"))
    )
    (net (code "147") (name "unconnected-(S35-A-Pad+)") (class "Default")
      (node (ref "S35") (pin "+") (pinfunction "A_+") (pintype "passive"))
    )
    (net (code "148") (name "unconnected-(S35-C-Pad-)") (class "Default")
      (node (ref "S35") (pin "-") (pinfunction "C_-") (pintype "passive"))
    )
    (net (code "149") (name "unconnected-(S35-P1-Pad2)") (class "Default")
      (node (ref "S35") (pin "2") (pinfunction "P1_2") (pintype "passive"))
    )
    (net (code "150") (name "unconnected-(S36-A-Pad+)") (class "Default")
      (node (ref "S36") (pin "+") (pinfunction "A_+") (pintype "passive"))
    )
    (net (code "151") (name "unconnected-(S36-C-Pad-)") (class "Default")
      (node (ref "S36") (pin "-") (pinfunction "C_-") (pintype "passive"))
    )
    (net (code "152") (name "unconnected-(S36-P1-Pad2)") (class "Default")
      (node (ref "S36") (pin "2") (pinfunction "P1_2") (pintype "passive"))
    )
    (net (code "153") (name "unconnected-(S37-A-Pad+)") (class "Default")
      (node (ref "S37") (pin "+") (pinfunction "A_+") (pintype "passive"))
    )
    (net (code "154") (name "unconnected-(S37-C-Pad-)") (class "Default")
      (node (ref "S37") (pin "-") (pinfunction "C_-") (pintype "passive"))
    )
    (net (code "155") (name "unconnected-(S37-P1-Pad2)") (class "Default")
      (node (ref "S37") (pin "2") (pinfunction "P1_2") (pintype "passive"))
    )
    (net (code "156") (name "unconnected-(S38-A-Pad+)") (class "Default")
      (node (ref "S38") (pin "+") (pinfunction "A_+") (pintype "passive"))
    )
    (net (code "157") (name "unconnected-(S38-C-Pad-)") (class "Default")
      (node (ref "S38") (pin "-") (pinfunction "C_-") (pintype "passive"))
    )
    (net (code "158") (name "unconnected-(S38-P1-Pad2)") (class "Default")
      (node (ref "S38") (pin "2") (pinfunction "P1_2") (pintype "passive"))
    )
    (net (code "159") (name "unconnected-(S39-A-Pad+)") (class "Default")
      (node (ref "S39") (pin "+") (pinfunction "A_+") (pintype "passive"))
    )
    (net (code "160") (name "unconnected-(S39-C-Pad-)") (class "Default")
      (node (ref "S39") (pin "-") (pinfunction "C_-") (pintype "passive"))
    )
    (net (code "161") (name "unconnected-(S39-P1-Pad2)") (class "Default")
      (node (ref "S39") (pin "2") (pinfunction "P1_2") (pintype "passive"))
    )
    (net (code "162") (name "unconnected-(S40-A-Pad+)") (class "Default")
      (node (ref "S40") (pin "+") (pinfunction "A_+") (pintype "passive"))
    )
    (net (code "163") (name "unconnected-(S40-C-Pad-)") (class "Default")
      (node (ref "S40") (pin "-") (pinfunction "C_-") (pintype "passive"))
    )
    (net (code "164") (name "unconnected-(S40-P1-Pad2)") (class "Default")
      (node (ref "S40") (pin "2") (pinfunction "P1_2") (pintype "passive"))
    )
    (net (code "165") (name "unconnected-(S41-A-Pad+)") (class "Default")
      (node (ref "S41") (pin "+") (pinfunction "A_+") (pintype "passive"))
    )
    (net (code "166") (name "unconnected-(S41-C-Pad-)") (class "Default")
      (node (ref "S41") (pin "-") (pinfunction "C_-") (pintype "passive"))
    )
    (net (code "167") (name "unconnected-(S41-P1-Pad2)") (class "Default")
      (node (ref "S41") (pin "2") (pinfunction "P1_2") (pintype "passive"))
    )
    (net (code "168") (name "unconnected-(S42-A-Pad+)") (class "Default")
      (node (ref "S42") (pin "+") (pinfunction "A_+") (pintype "passive"))
    )
    (net (code "169") (name "unconnected-(S42-C-Pad-)") (class "Default")
      (node (ref "S42") (pin "-") (pinfunction "C_-") (pintype "passive"))
    )
    (net (code "170") (name "unconnected-(S42-P1-Pad2)") (class "Default")
      (node (ref "S42") (pin "2") (pinfunction "P1_2") (pintype "passive"))
    )
    (net (code "171") (name "unconnected-(S43-A-Pad+)") (class "Default")
      (node (ref "S43") (pin "+") (pinfunction "A_+") (pintype "passive"))
    )
    (net (code "172") (name "unconnected-(S43-C-Pad-)") (class "Default")
      (node (ref "S43") (pin "-") (pinfunction "C_-") (pintype "passive"))
    )
    (net (code "173") (name "unconnected-(S43-P1-Pad2)") (class "Default")
      (node (ref "S43") (pin "2") (pinfunction "P1_2") (pintype "passive"))
    )
    (net (code "174") (name "unconnected-(S44-A-Pad+)") (class "Default")
      (node (ref "S44") (pin "+") (pinfunction "A_+") (pintype "passive"))
    )
    (net (code "175") (name "unconnected-(S44-C-Pad-)") (class "Default")
      (node (ref "S44") (pin "-") (pinfunction "C_-") (pintype "passive"))
    )
    (net (code "176") (name "unconnected-(S44-P1-Pad2)") (class "Default")
      (node (ref "S44") (pin "2") (pinfunction "P1_2") (pintype "passive"))
    )
    (net (code "177") (name "unconnected-(S45-A-Pad+)") (class "Default")
      (node (ref "S45") (pin "+") (pinfunction "A_+") (pintype "passive"))
    )
    (net (code "178") (name "unconnected-(S45-C-Pad-)") (class "Default")
      (node (ref "S45") (pin "-") (pinfunction "C_-") (pintype "passive"))
    )
    (net (code "179") (name "unconnected-(S45-P1-Pad2)") (class "Default")
      (node (ref "S45") (pin "2") (pinfunction "P1_2") (pintype "passive"))
    )
    (net (code "180") (name "unconnected-(S46-A-Pad+)") (class "Default")
      (node (ref "S46") (pin "+") (pinfunction "A_+") (pintype "passive"))
    )
    (net (code "181") (name "unconnected-(S46-C-Pad-)") (class "Default")
      (node (ref "S46") (pin "-") (pinfunction "C_-") (pintype "passive"))
    )
    (net (code "182") (name "unconnected-(S46-P1-Pad2)") (class "Default")
      (node (ref "S46") (pin "2") (pinfunction "P1_2") (pintype "passive"))
    )
    (net (code "183") (name "unconnected-(S47-A-Pad+)") (class "Default")
      (node (ref "S47") (pin "+") (pinfunction "A_+") (pintype "passive"))
    )
    (net (code "184") (name "unconnected-(S47-C-Pad-)") (class "Default")
      (node (ref "S47") (pin "-") (pinfunction "C_-") (pintype "passive"))
    )
    (net (code "185") (name "unconnected-(S47-P1-Pad2)") (class "Default")
      (node (ref "S47") (pin "2") (pinfunction "P1_2") (pintype "passive"))
    )
    (net (code "186") (name "unconnected-(S48-A-Pad+)") (class "Default")
      (node (ref "S48") (pin "+") (pinfunction "A_+") (pintype "passive"))
    )
    (net (code "187") (name "unconnected-(S48-C-Pad-)") (class "Default")
      (node (ref "S48") (pin "-") (pinfunction "C_-") (pintype "passive"))
    )
    (net (code "188") (name "unconnected-(S48-P1-Pad2)") (class "Default")
      (node (ref "S48") (pin "2") (pinfunction "P1_2") (pintype "passive"))
    )
    (net (code "189") (name "unconnected-(S49-A-Pad+)") (class "Default")
      (node (ref "S49") (pin "+") (pinfunction "A_+") (pintype "passive"))
    )
    (net (code "190") (name "unconnected-(S49-C-Pad-)") (class "Default")
      (node (ref "S49") (pin "-") (pinfunction "C_-") (pintype "passive"))
    )
    (net (code "191") (name "unconnected-(S49-P1-Pad2)") (class "Default")
      (node (ref "S49") (pin "2") (pinfunction "P1_2") (pintype "passive"))
    )
    (net (code "192") (name "unconnected-(S50-A-Pad+)") (class "Default")
      (node (ref "S50") (pin "+") (pinfunction "A_+") (pintype "passive"))
    )
    (net (code "193") (name "unconnected-(S50-C-Pad-)") (class "Default")
      (node (ref "S50") (pin "-") (pinfunction "C_-") (pintype "passive"))
    )
    (net (code "194") (name "unconnected-(S50-P1-Pad2)") (class "Default")
      (node (ref "S50") (pin "2") (pinfunction "P1_2") (pintype "passive"))
    )
    (net (code "195") (name "unconnected-(S51-A-Pad+)") (class "Default")
      (node (ref "S51") (pin "+") (pinfunction "A_+") (pintype "passive"))
    )
    (net (code "196") (name "unconnected-(S51-C-Pad-)") (class "Default")
      (node (ref "S51") (pin "-") (pinfunction "C_-") (pintype "passive"))
    )
    (net (code "197") (name "unconnected-(S51-P1-Pad2)") (class "Default")
      (node (ref "S51") (pin "2") (pinfunction "P1_2") (pintype "passive"))
    )
    (net (code "198") (name "unconnected-(S52-A-Pad+)") (class "Default")
      (node (ref "S52") (pin "+") (pinfunction "A_+") (pintype "passive"))
    )
    (net (code "199") (name "unconnected-(S52-C-Pad-)") (class "Default")
      (node (ref "S52") (pin "-") (pinfunction "C_-") (pintype "passive"))
    )
    (net (code "200") (name "unconnected-(S52-P1-Pad2)") (class "Default")
      (node (ref "S52") (pin "2") (pinfunction "P1_2") (pintype "passive"))
    )
    (net (code "201") (name "unconnected-(S53-A-Pad+)") (class "Default")
      (node (ref "S53") (pin "+") (pinfunction "A_+") (pintype "passive"))
    )
    (net (code "202") (name "unconnected-(S53-C-Pad-)") (class "Default")
      (node (ref "S53") (pin "-") (pinfunction "C_-") (pintype "passive"))
    )
    (net (code "203") (name "unconnected-(S53-P1-Pad2)") (class "Default")
      (node (ref "S53") (pin "2") (pinfunction "P1_2") (pintype "passive"))
    )
    (net (code "204") (name "unconnected-(S54-A-Pad+)") (class "Default")
      (node (ref "S54") (pin "+") (pinfunction "A_+") (pintype "passive"))
    )
    (net (code "205") (name "unconnected-(S54-C-Pad-)") (class "Default")
      (node (ref "S54") (pin "-") (pinfunction "C_-") (pintype "passive"))
    )
    (net (code "206") (name "unconnected-(S54-P1-Pad2)") (class "Default")
      (node (ref "S54") (pin "2") (pinfunction "P1_2") (pintype "passive"))
    )
    (net (code "207") (name "unconnected-(S55-A-Pad+)") (class "Default")
      (node (ref "S55") (pin "+") (pinfunction "A_+") (pintype "passive"))
    )
    (net (code "208") (name "unconnected-(S55-C-Pad-)") (class "Default")
      (node (ref "S55") (pin "-") (pinfunction "C_-") (pintype "passive"))
    )
    (net (code "209") (name "unconnected-(S55-P1-Pad2)") (class "Default")
      (node (ref "S55") (pin "2") (pinfunction "P1_2") (pintype "passive"))
    )
    (net (code "210") (name "unconnected-(S56-A-Pad+)") (class "Default")
      (node (ref "S56") (pin "+") (pinfunction "A_+") (pintype "passive"))
    )
    (net (code "211") (name "unconnected-(S56-C-Pad-)") (class "Default")
      (node (ref "S56") (pin "-") (pinfunction "C_-") (pintype "passive"))
    )
    (net (code "212") (name "unconnected-(S56-P1-Pad2)") (class "Default")
      (node (ref "S56") (pin "2") (pinfunction "P1_2") (pintype "passive"))
    )
    (net (code "213") (name "unconnected-(S57-A-Pad+)") (class "Default")
      (node (ref "S57") (pin "+") (pinfunction "A_+") (pintype "passive"))
    )
    (net (code "214") (name "unconnected-(S57-C-Pad-)") (class "Default")
      (node (ref "S57") (pin "-") (pinfunction "C_-") (pintype "passive"))
    )
    (net (code "215") (name "unconnected-(S57-P1-Pad2)") (class "Default")
      (node (ref "S57") (pin "2") (pinfunction "P1_2") (pintype "passive"))
    )
    (net (code "216") (name "unconnected-(S58-A-Pad+)") (class "Default")
      (node (ref "S58") (pin "+") (pinfunction "A_+") (pintype "passive"))
    )
    (net (code "217") (name "unconnected-(S58-C-Pad-)") (class "Default")
      (node (ref "S58") (pin "-") (pinfunction "C_-") (pintype "passive"))
    )
    (net (code "218") (name "unconnected-(S58-P1-Pad2)") (class "Default")
      (node (ref "S58") (pin "2") (pinfunction "P1_2") (pintype "passive"))
    )
    (net (code "219") (name "unconnected-(S59-A-Pad+)") (class "Default")
      (node (ref "S59") (pin "+") (pinfunction "A_+") (pintype "passive"))
    )
    (net (code "220") (name "unconnected-(S59-C-Pad-)") (class "Default")
      (node (ref "S59") (pin "-") (pinfunction "C_-") (pintype "passive"))
    )
    (net (code "221") (name "unconnected-(S59-P1-Pad2)") (class "Default")
      (node (ref "S59") (pin "2") (pinfunction "P1_2") (pintype "passive"))
    )
    (net (code "222") (name "unconnected-(S60-A-Pad+)") (class "Default")
      (node (ref "S60") (pin "+") (pinfunction "A_+") (pintype "passive"))
    )
    (net (code "223") (name "unconnected-(S60-C-Pad-)") (class "Default")
      (node (ref "S60") (pin "-") (pinfunction "C_-") (pintype "passive"))
    )
    (net (code "224") (name "unconnected-(S60-P1-Pad2)") (class "Default")
      (node (ref "S60") (pin "2") (pinfunction "P1_2") (pintype "passive"))
    )
    (net (code "225") (name "unconnected-(S61-A-Pad+)") (class "Default")
      (node (ref "S61") (pin "+") (pinfunction "A_+") (pintype "passive"))
    )
    (net (code "226") (name "unconnected-(S61-C-Pad-)") (class "Default")
      (node (ref "S61") (pin "-") (pinfunction "C_-") (pintype "passive"))
    )
    (net (code "227") (name "unconnected-(S61-P1-Pad2)") (class "Default")
      (node (ref "S61") (pin "2") (pinfunction "P1_2") (pintype "passive"))
    )
    (net (code "228") (name "unconnected-(S62-A-Pad+)") (class "Default")
      (node (ref "S62") (pin "+") (pinfunction "A_+") (pintype "passive"))
    )
    (net (code "229") (name "unconnected-(S62-C-Pad-)") (class "Default")
      (node (ref "S62") (pin "-") (pinfunction "C_-") (pintype "passive"))
    )
    (net (code "230") (name "unconnected-(S62-P1-Pad2)") (class "Default")
      (node (ref "S62") (pin "2") (pinfunction "P1_2") (pintype "passive"))
    )
    (net (code "231") (name "unconnected-(S63-A-Pad+)") (class "Default")
      (node (ref "S63") (pin "+") (pinfunction "A_+") (pintype "passive"))
    )
    (net (code "232") (name "unconnected-(S63-C-Pad-)") (class "Default")
      (node (ref "S63") (pin "-") (pinfunction "C_-") (pintype "passive"))
    )
    (net (code "233") (name "unconnected-(S63-P1-Pad2)") (class "Default")
      (node (ref "S63") (pin "2") (pinfunction "P1_2") (pintype "passive"))
    )
    (net (code "234") (name "unconnected-(S64-A-Pad+)") (class "Default")
      (node (ref "S64") (pin "+") (pinfunction "A_+") (pintype "passive"))
    )
    (net (code "235") (name "unconnected-(S64-C-Pad-)") (class "Default")
      (node (ref "S64") (pin "-") (pinfunction "C_-") (pintype "passive"))
    )
    (net (code "236") (name "unconnected-(S64-P1-Pad2)") (class "Default")
      (node (ref "S64") (pin "2") (pinfunction "P1_2") (pintype "passive"))
    )
    (net (code "237") (name "unconnected-(S65-A-Pad+)") (class "Default")
      (node (ref "S65") (pin "+") (pinfunction "A_+") (pintype "passive"))
    )
    (net (code "238") (name "unconnected-(S65-C-Pad-)") (class "Default")
      (node (ref "S65") (pin "-") (pinfunction "C_-") (pintype "passive"))
    )
    (net (code "239") (name "unconnected-(S65-P1-Pad2)") (class "Default")
      (node (ref "S65") (pin "2") (pinfunction "P1_2") (pintype "passive"))
    )
    (net (code "240") (name "unconnected-(S66-A-Pad+)") (class "Default")
      (node (ref "S66") (pin "+") (pinfunction "A_+") (pintype "passive"))
    )
    (net (code "241") (name "unconnected-(S66-C-Pad-)") (class "Default")
      (node (ref "S66") (pin "-") (pinfunction "C_-") (pintype "passive"))
    )
    (net (code "242") (name "unconnected-(S66-P1-Pad2)") (class "Default")
      (node (ref "S66") (pin "2") (pinfunction "P1_2") (pintype "passive"))
    )
    (net (code "243") (name "unconnected-(S67-A-Pad+)") (class "Default")
      (node (ref "S67") (pin "+") (pinfunction "A_+") (pintype "passive"))
    )
    (net (code "244") (name "unconnected-(S67-C-Pad-)") (class "Default")
      (node (ref "S67") (pin "-") (pinfunction "C_-") (pintype "passive"))
    )
    (net (code "245") (name "unconnected-(S67-P1-Pad2)") (class "Default")
      (node (ref "S67") (pin "2") (pinfunction "P1_2") (pintype "passive"))
    )
    (net (code "246") (name "unconnected-(S68-A-Pad+)") (class "Default")
      (node (ref "S68") (pin "+") (pinfunction "A_+") (pintype "passive"))
    )
    (net (code "247") (name "unconnected-(S68-C-Pad-)") (class "Default")
      (node (ref "S68") (pin "-") (pinfunction "C_-") (pintype "passive"))
    )
    (net (code "248") (name "unconnected-(S68-P1-Pad2)") (class "Default")
      (node (ref "S68") (pin "2") (pinfunction "P1_2") (pintype "passive"))
    )
    (net (code "249") (name "unconnected-(S69-A-Pad+)") (class "Default")
      (node (ref "S69") (pin "+") (pinfunction "A_+") (pintype "passive"))
    )
    (net (code "250") (name "unconnected-(S69-C-Pad-)") (class "Default")
      (node (ref "S69") (pin "-") (pinfunction "C_-") (pintype "passive"))
    )
    (net (code "251") (name "unconnected-(S69-P1-Pad2)") (class "Default")
      (node (ref "S69") (pin "2") (pinfunction "P1_2") (pintype "passive"))
    )
    (net (code "252") (name "unconnected-(S70-A-Pad+)") (class "Default")
      (node (ref "S70") (pin "+") (pinfunction "A_+") (pintype "passive"))
    )
    (net (code "253") (name "unconnected-(S70-C-Pad-)") (class "Default")
      (node (ref "S70") (pin "-") (pinfunction "C_-") (pintype "passive"))
    )
    (net (code "254") (name "unconnected-(S70-P1-Pad2)") (class "Default")
      (node (ref "S70") (pin "2") (pinfunction "P1_2") (pintype "passive"))
    )
    (net (code "255") (name "unconnected-(S71-A-Pad+)") (class "Default")
      (node (ref "S71") (pin "+") (pinfunction "A_+") (pintype "passive"))
    )
    (net (code "256") (name "unconnected-(S71-C-Pad-)") (class "Default")
      (node (ref "S71") (pin "-") (pinfunction "C_-") (pintype "passive"))
    )
    (net (code "257") (name "unconnected-(S71-P1-Pad2)") (class "Default")
      (node (ref "S71") (pin "2") (pinfunction "P1_2") (pintype "passive"))
    )
    (net (code "258") (name "unconnected-(S72-A-Pad+)") (class "Default")
      (node (ref "S72") (pin "+") (pinfunction "A_+") (pintype "passive"))
    )
    (net (code "259") (name "unconnected-(S72-C-Pad-)") (class "Default")
      (node (ref "S72") (pin "-") (pinfunction "C_-") (pintype "passive"))
    )
    (net (code "260") (name "unconnected-(S72-P1-Pad2)") (class "Default")
      (node (ref "S72") (pin "2") (pinfunction "P1_2") (pintype "passive"))
    )
    (net (code "261") (name "unconnected-(S73-A-Pad+)") (class "Default")
      (node (ref "S73") (pin "+") (pinfunction "A_+") (pintype "passive"))
    )
    (net (code "262") (name "unconnected-(S73-C-Pad-)") (class "Default")
      (node (ref "S73") (pin "-") (pinfunction "C_-") (pintype "passive"))
    )
    (net (code "263") (name "unconnected-(S73-P1-Pad2)") (class "Default")
      (node (ref "S73") (pin "2") (pinfunction "P1_2") (pintype "passive"))
    )
    (net (code "264") (name "unconnected-(S74-A-Pad+)") (class "Default")
      (node (ref "S74") (pin "+") (pinfunction "A_+") (pintype "passive"))
    )
    (net (code "265") (name "unconnected-(S74-C-Pad-)") (class "Default")
      (node (ref "S74") (pin "-") (pinfunction "C_-") (pintype "passive"))
    )
    (net (code "266") (name "unconnected-(S74-P1-Pad2)") (class "Default")
      (node (ref "S74") (pin "2") (pinfunction "P1_2") (pintype "passive"))
    )
  )
)
